# boost-charge-activeFull.net
KiCad netlist of a schematic drawn in EAGLE
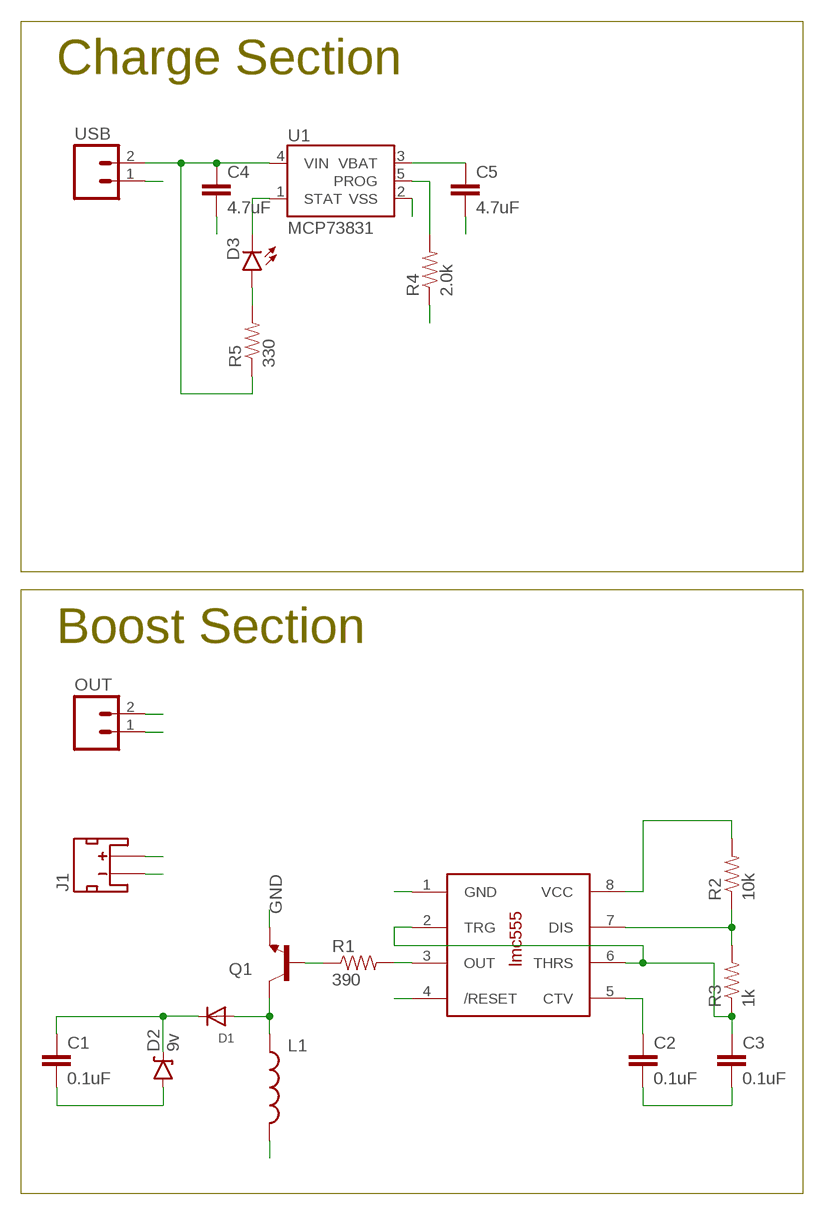
[diagram p0: schematic, sheet 1]

(export (version "E")
  (design (tool "Eeschema 10.0.6"))
  (components
    (comp (ref "C1")
      (value "0.1uF")
      (footprint "eagle-import:0603-CAP")
      (libsource (lib "eagle-import") (part "0.1UF-25V(+80/-20%)(0603)"))
    )
    (comp (ref "C2")
      (value "0.1uF")
      (footprint "eagle-import:0603-CAP")
      (libsource (lib "eagle-import") (part "0.1UF-25V(+80/-20%)(0603)"))
    )
    (comp (ref "C3")
      (value "0.1uF")
      (footprint "eagle-import:0603-CAP")
      (libsource (lib "eagle-import") (part "0.1UF-25V(+80/-20%)(0603)"))
    )
    (comp (ref "C4")
      (value "4.7uF")
      (footprint "eagle-import:0603-CAP")
      (libsource (lib "eagle-import") (part "0.1UF-25V-5%(0603)"))
    )
    (comp (ref "C5")
      (value "4.7uF")
      (footprint "eagle-import:0603-CAP")
      (libsource (lib "eagle-import") (part "0.1UF-25V-5%(0603)"))
    )
    (comp (ref "D1")
      (value "DIODESOD-323F")
      (footprint "eagle-import:SOD-323F")
      (libsource (lib "eagle-import") (part "DIODESOD-323F"))
    )
    (comp (ref "D2")
      (value "9v")
      (footprint "eagle-import:SOD-323")
      (libsource (lib "eagle-import") (part "DIODE-ZENER3.3V"))
    )
    (comp (ref "D3")
      (value "LED0603")
      (footprint "eagle-import:LED-0603")
      (libsource (lib "eagle-import") (part "LED0603"))
    )
    (comp (ref "J1")
      (value "JST_2MM_MALE")
      (footprint "eagle-import:JST-2-SMD")
      (libsource (lib "eagle-import") (part "JST_2MM_MALE"))
    )
    (comp (ref "L1")
      (value "INDUCTOR0603")
      (footprint "eagle-import:0603")
      (libsource (lib "eagle-import") (part "INDUCTOR0603"))
    )
    (comp (ref "OUT")
      (value "M02PTH")
      (footprint "eagle-import:1X02")
      (libsource (lib "eagle-import") (part "M02PTH"))
    )
    (comp (ref "Q1")
      (value "TRANSISTOR_NPN2N3904")
      (footprint "eagle-import:TO-92")
      (libsource (lib "eagle-import") (part "TRANSISTOR_NPN2N3904"))
    )
    (comp (ref "R1")
      (value "390")
      (footprint "eagle-import:0603-RES")
      (libsource (lib "eagle-import") (part "5.62KOHM1/10W1%(0603)"))
    )
    (comp (ref "R2")
      (value "10k")
      (footprint "eagle-import:0603")
      (libsource (lib "eagle-import") (part "0OHM-1/10W-5%(0603)"))
    )
    (comp (ref "R3")
      (value "1k")
      (footprint "eagle-import:0603")
      (libsource (lib "eagle-import") (part "0OHM-1/10W-5%(0603)"))
    )
    (comp (ref "R4")
      (value "2.0k")
      (footprint "eagle-import:0603-RES")
      (libsource (lib "eagle-import") (part "2.0KOHM1/10W5%(0603)"))
    )
    (comp (ref "R5")
      (value "330")
      (footprint "eagle-import:0603-RES")
      (libsource (lib "eagle-import") (part "330OHM1/10W1%(0603)"))
    )
    (comp (ref "U$1")
      (value "LMC555")
      (footprint "eagle-import:LMC555")
      (libsource (lib "eagle-import") (part "LMC555"))
    )
    (comp (ref "U1")
      (value "MCP73831")
      (footprint "eagle-import:SOT23-5")
      (libsource (lib "eagle-import") (part "MCP73831"))
    )
    (comp (ref "USB")
      (value "M02PTH")
      (footprint "eagle-import:1X02")
      (libsource (lib "eagle-import") (part "M02PTH"))
    )
  )
  (nets
    (net (code "1") (name "/3V") (class "Default")
      (node (ref "C5") (pin "1") (pinfunction "1_1") (pintype "passive"))
      (node (ref "J1") (pin "2") (pinfunction "+_2") (pintype "bidirectional"))
      (node (ref "L1") (pin "2") (pinfunction "2_2") (pintype "passive"))
      (node (ref "R2") (pin "2") (pinfunction "2_2") (pintype "passive"))
      (node (ref "U$1") (pin "4") (pinfunction "/RESET_4") (pintype "bidirectional"))
      (node (ref "U$1") (pin "8") (pinfunction "VCC_8") (pintype "bidirectional"))
      (node (ref "U1") (pin "3") (pinfunction "VBAT_3") (pintype "power_in"))
    )
    (net (code "2") (name "/9V") (class "Default")
      (node (ref "C1") (pin "1") (pinfunction "1_1") (pintype "passive"))
      (node (ref "D1") (pin "C") (pinfunction "C_C") (pintype "passive"))
      (node (ref "D2") (pin "C") (pinfunction "C_C") (pintype "passive"))
      (node (ref "OUT") (pin "2") (pinfunction "2_2") (pintype "passive"))
    )
    (net (code "3") (name "/GND") (class "Default")
      (node (ref "C1") (pin "2") (pinfunction "2_2") (pintype "passive"))
      (node (ref "C2") (pin "2") (pinfunction "2_2") (pintype "passive"))
      (node (ref "C3") (pin "2") (pinfunction "2_2") (pintype "passive"))
      (node (ref "C4") (pin "2") (pinfunction "2_2") (pintype "passive"))
      (node (ref "C5") (pin "2") (pinfunction "2_2") (pintype "passive"))
      (node (ref "D2") (pin "A") (pinfunction "A_A") (pintype "passive"))
      (node (ref "J1") (pin "1") (pinfunction "-_1") (pintype "bidirectional"))
      (node (ref "OUT") (pin "1") (pinfunction "1_1") (pintype "passive"))
      (node (ref "Q1") (pin "1") (pinfunction "E_1") (pintype "passive"))
      (node (ref "R4") (pin "1") (pinfunction "1_1") (pintype "passive"))
      (node (ref "U$1") (pin "1") (pinfunction "GND_1") (pintype "bidirectional"))
      (node (ref "U1") (pin "2") (pinfunction "VSS_2") (pintype "power_in"))
      (node (ref "USB") (pin "1") (pinfunction "1_1") (pintype "passive"))
    )
    (net (code "4") (name "Net-(D3-PadA)") (class "Default")
      (node (ref "D3") (pin "A") (pinfunction "A_A") (pintype "passive"))
      (node (ref "R5") (pin "2") (pinfunction "2_2") (pintype "passive"))
    )
    (net (code "5") (name "Net-(Q1-B)") (class "Default")
      (node (ref "Q1") (pin "2") (pinfunction "B_2") (pintype "passive"))
      (node (ref "R1") (pin "1") (pinfunction "1_1") (pintype "passive"))
    )
    (net (code "6") (name "Net-(Q1-C)") (class "Default")
      (node (ref "D1") (pin "A") (pinfunction "A_A") (pintype "passive"))
      (node (ref "L1") (pin "1") (pinfunction "1_1") (pintype "passive"))
      (node (ref "Q1") (pin "3") (pinfunction "C_3") (pintype "passive"))
    )
    (net (code "7") (name "Net-(U$1-CTV)") (class "Default")
      (node (ref "C2") (pin "1") (pinfunction "1_1") (pintype "passive"))
      (node (ref "U$1") (pin "5") (pinfunction "CTV_5") (pintype "bidirectional"))
    )
    (net (code "8") (name "Net-(U$1-DIS)") (class "Default")
      (node (ref "R2") (pin "1") (pinfunction "1_1") (pintype "passive"))
      (node (ref "R3") (pin "2") (pinfunction "2_2") (pintype "passive"))
      (node (ref "U$1") (pin "7") (pinfunction "DIS_7") (pintype "bidirectional"))
    )
    (net (code "9") (name "Net-(U$1-OUT)") (class "Default")
      (node (ref "R1") (pin "2") (pinfunction "2_2") (pintype "passive"))
      (node (ref "U$1") (pin "3") (pinfunction "OUT_3") (pintype "bidirectional"))
    )
    (net (code "10") (name "Net-(U$1-THRS)") (class "Default")
      (node (ref "C3") (pin "1") (pinfunction "1_1") (pintype "passive"))
      (node (ref "R3") (pin "1") (pinfunction "1_1") (pintype "passive"))
      (node (ref "U$1") (pin "2") (pinfunction "TRG_2") (pintype "bidirectional"))
      (node (ref "U$1") (pin "6") (pinfunction "THRS_6") (pintype "bidirectional"))
    )
    (net (code "11") (name "Net-(U1-PROG)") (class "Default")
      (node (ref "R4") (pin "2") (pinfunction "2_2") (pintype "passive"))
      (node (ref "U1") (pin "5") (pinfunction "PROG_5") (pintype "input"))
    )
    (net (code "12") (name "Net-(U1-STAT)") (class "Default")
      (node (ref "D3") (pin "C") (pinfunction "C_C") (pintype "passive"))
      (node (ref "U1") (pin "1") (pinfunction "STAT_1") (pintype "output"))
    )
    (net (code "13") (name "Net-(U1-VIN)") (class "Default")
      (node (ref "C4") (pin "1") (pinfunction "1_1") (pintype "passive"))
      (node (ref "R5") (pin "1") (pinfunction "1_1") (pintype "passive"))
      (node (ref "U1") (pin "4") (pinfunction "VIN_4") (pintype "power_in"))
      (node (ref "USB") (pin "2") (pinfunction "2_2") (pintype "passive"))
    )
    (net (code "14") (name "unconnected-(J1-PAD1-PadNC1)") (class "Default")
      (node (ref "J1") (pin "NC1") (pinfunction "PAD1_NC1") (pintype "bidirectional"))
    )
    (net (code "15") (name "unconnected-(J1-PAD2-PadNC2)") (class "Default")
      (node (ref "J1") (pin "NC2") (pinfunction "PAD2_NC2") (pintype "bidirectional"))
    )
  )
)
